# PCA9532.net
KiCad netlist of a schematic drawn in EAGLE
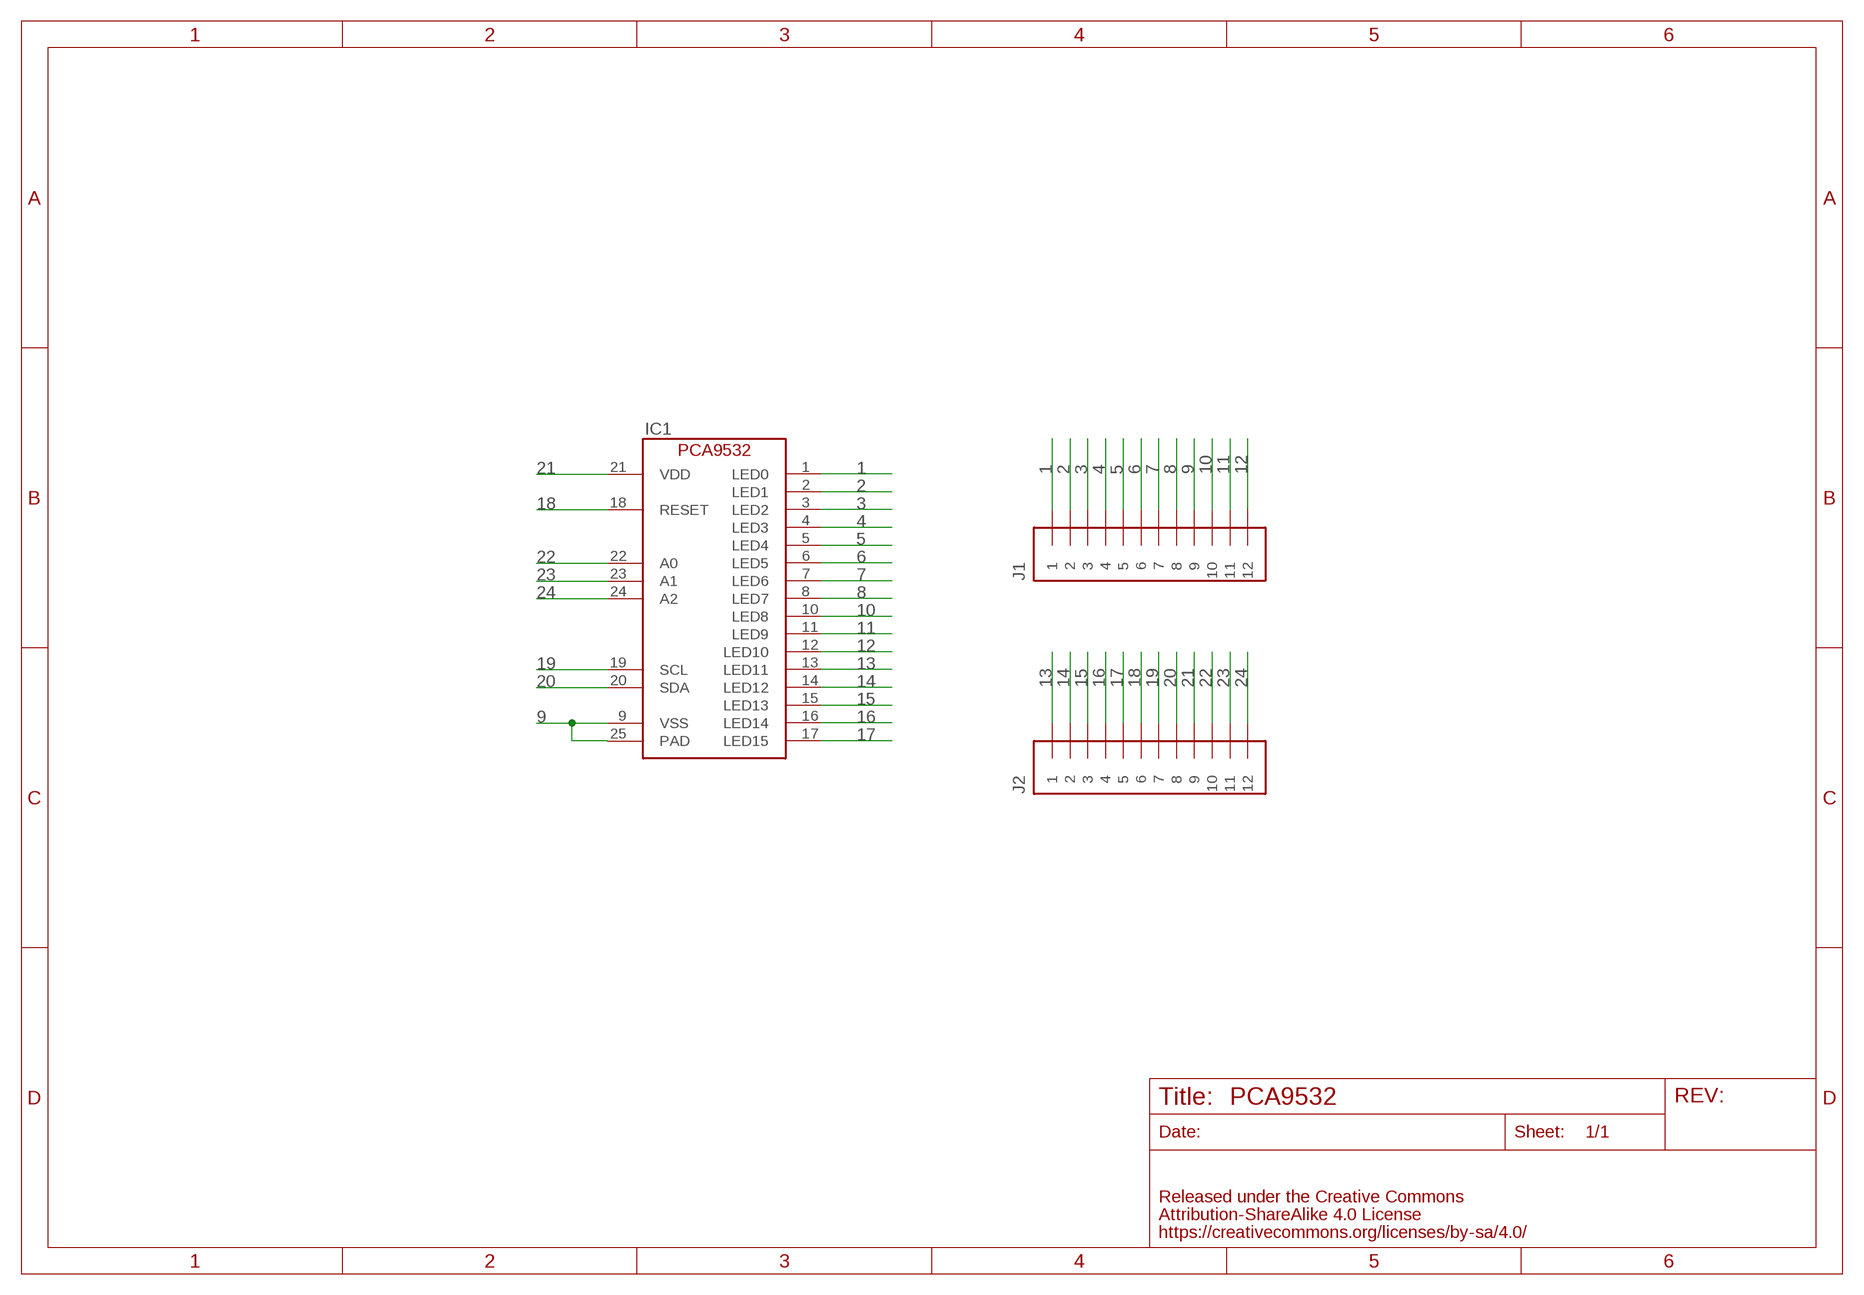
[diagram p0: schematic, sheet 1]

(export (version "E")
  (design (tool "Eeschema 10.0.6"))
  (components
    (comp (ref "IC1")
      (value "PCA9532BS")
      (footprint "eagle-import:HVQFN24")
      (libsource (lib "eagle-import") (part "PCA9532BS"))
    )
    (comp (ref "J1")
      (value "PIN_HEADER_1X12")
      (footprint "eagle-import:PIN_1X12_SNEAKY")
      (libsource (lib "eagle-import") (part "PIN_HEADER_1X12"))
    )
    (comp (ref "J2")
      (value "PIN_HEADER_1X12")
      (footprint "eagle-import:PIN_1X12_SNEAKY")
      (libsource (lib "eagle-import") (part "PIN_HEADER_1X12"))
    )
  )
  (nets
    (net (code "1") (name "/1") (class "Default")
      (node (ref "IC1") (pin "1") (pinfunction "LED0_1") (pintype "bidirectional"))
      (node (ref "J1") (pin "1") (pinfunction "1_1") (pintype "bidirectional"))
    )
    (net (code "2") (name "/2") (class "Default")
      (node (ref "IC1") (pin "2") (pinfunction "LED1_2") (pintype "bidirectional"))
      (node (ref "J1") (pin "2") (pinfunction "2_2") (pintype "bidirectional"))
    )
    (net (code "3") (name "/3") (class "Default")
      (node (ref "IC1") (pin "3") (pinfunction "LED2_3") (pintype "bidirectional"))
      (node (ref "J1") (pin "3") (pinfunction "3_3") (pintype "bidirectional"))
    )
    (net (code "4") (name "/4") (class "Default")
      (node (ref "IC1") (pin "4") (pinfunction "LED3_4") (pintype "bidirectional"))
      (node (ref "J1") (pin "4") (pinfunction "4_4") (pintype "bidirectional"))
    )
    (net (code "5") (name "/5") (class "Default")
      (node (ref "IC1") (pin "5") (pinfunction "LED4_5") (pintype "bidirectional"))
      (node (ref "J1") (pin "5") (pinfunction "5_5") (pintype "bidirectional"))
    )
    (net (code "6") (name "/6") (class "Default")
      (node (ref "IC1") (pin "6") (pinfunction "LED5_6") (pintype "bidirectional"))
      (node (ref "J1") (pin "6") (pinfunction "6_6") (pintype "bidirectional"))
    )
    (net (code "7") (name "/7") (class "Default")
      (node (ref "IC1") (pin "7") (pinfunction "LED6_7") (pintype "bidirectional"))
      (node (ref "J1") (pin "7") (pinfunction "7_7") (pintype "bidirectional"))
    )
    (net (code "8") (name "/8") (class "Default")
      (node (ref "IC1") (pin "8") (pinfunction "LED7_8") (pintype "bidirectional"))
      (node (ref "J1") (pin "8") (pinfunction "8_8") (pintype "bidirectional"))
    )
    (net (code "9") (name "/9") (class "Default")
      (node (ref "IC1") (pin "25") (pinfunction "PAD_25") (pintype "bidirectional"))
      (node (ref "IC1") (pin "9") (pinfunction "VSS_9") (pintype "bidirectional"))
      (node (ref "J1") (pin "9") (pinfunction "9_9") (pintype "bidirectional"))
    )
    (net (code "10") (name "/10") (class "Default")
      (node (ref "IC1") (pin "10") (pinfunction "LED8_10") (pintype "bidirectional"))
      (node (ref "J1") (pin "10") (pinfunction "10_10") (pintype "bidirectional"))
    )
    (net (code "11") (name "/11") (class "Default")
      (node (ref "IC1") (pin "11") (pinfunction "LED9_11") (pintype "bidirectional"))
      (node (ref "J1") (pin "11") (pinfunction "11_11") (pintype "bidirectional"))
    )
    (net (code "12") (name "/12") (class "Default")
      (node (ref "IC1") (pin "12") (pinfunction "LED10_12") (pintype "bidirectional"))
      (node (ref "J1") (pin "12") (pinfunction "12_12") (pintype "bidirectional"))
    )
    (net (code "13") (name "/13") (class "Default")
      (node (ref "IC1") (pin "13") (pinfunction "LED11_13") (pintype "bidirectional"))
      (node (ref "J2") (pin "1") (pinfunction "1_1") (pintype "bidirectional"))
    )
    (net (code "14") (name "/14") (class "Default")
      (node (ref "IC1") (pin "14") (pinfunction "LED12_14") (pintype "bidirectional"))
      (node (ref "J2") (pin "2") (pinfunction "2_2") (pintype "bidirectional"))
    )
    (net (code "15") (name "/15") (class "Default")
      (node (ref "IC1") (pin "15") (pinfunction "LED13_15") (pintype "bidirectional"))
      (node (ref "J2") (pin "3") (pinfunction "3_3") (pintype "bidirectional"))
    )
    (net (code "16") (name "/16") (class "Default")
      (node (ref "IC1") (pin "16") (pinfunction "LED14_16") (pintype "bidirectional"))
      (node (ref "J2") (pin "4") (pinfunction "4_4") (pintype "bidirectional"))
    )
    (net (code "17") (name "/17") (class "Default")
      (node (ref "IC1") (pin "17") (pinfunction "LED15_17") (pintype "bidirectional"))
      (node (ref "J2") (pin "5") (pinfunction "5_5") (pintype "bidirectional"))
    )
    (net (code "18") (name "/18") (class "Default")
      (node (ref "IC1") (pin "18") (pinfunction "RESET_18") (pintype "bidirectional"))
      (node (ref "J2") (pin "6") (pinfunction "6_6") (pintype "bidirectional"))
    )
    (net (code "19") (name "/19") (class "Default")
      (node (ref "IC1") (pin "19") (pinfunction "SCL_19") (pintype "bidirectional"))
      (node (ref "J2") (pin "7") (pinfunction "7_7") (pintype "bidirectional"))
    )
    (net (code "20") (name "/20") (class "Default")
      (node (ref "IC1") (pin "20") (pinfunction "SDA_20") (pintype "bidirectional"))
      (node (ref "J2") (pin "8") (pinfunction "8_8") (pintype "bidirectional"))
    )
    (net (code "21") (name "/21") (class "Default")
      (node (ref "IC1") (pin "21") (pinfunction "VDD_21") (pintype "bidirectional"))
      (node (ref "J2") (pin "9") (pinfunction "9_9") (pintype "bidirectional"))
    )
    (net (code "22") (name "/22") (class "Default")
      (node (ref "IC1") (pin "22") (pinfunction "A0_22") (pintype "bidirectional"))
      (node (ref "J2") (pin "10") (pinfunction "10_10") (pintype "bidirectional"))
    )
    (net (code "23") (name "/23") (class "Default")
      (node (ref "IC1") (pin "23") (pinfunction "A1_23") (pintype "bidirectional"))
      (node (ref "J2") (pin "11") (pinfunction "11_11") (pintype "bidirectional"))
    )
    (net (code "24") (name "/24") (class "Default")
      (node (ref "IC1") (pin "24") (pinfunction "A2_24") (pintype "bidirectional"))
      (node (ref "J2") (pin "12") (pinfunction "12_12") (pintype "bidirectional"))
    )
  )
)
